# e_Quadratic_3_Level_Boost.net
KiCad netlist of a schematic drawn in EAGLE
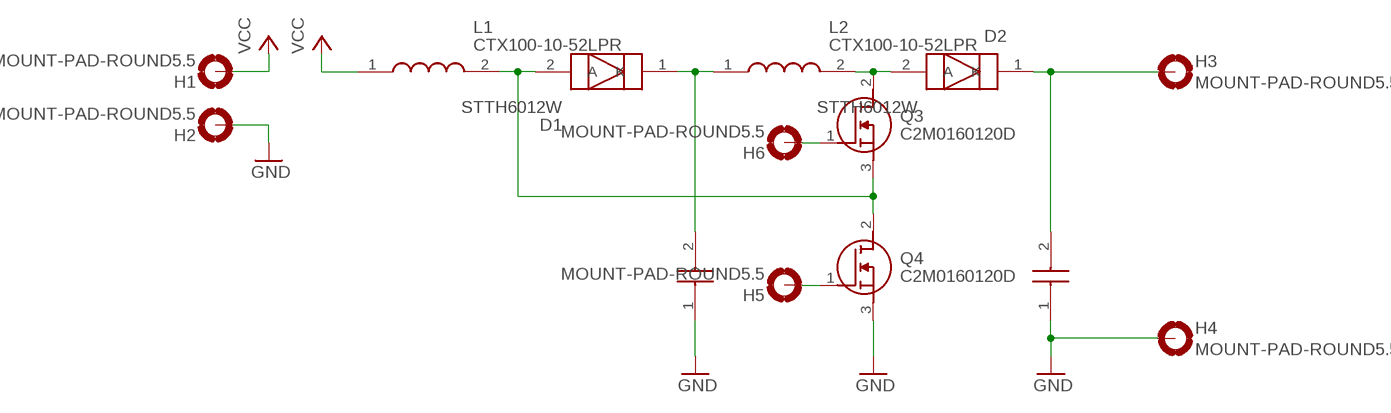
[diagram p0: schematic, sheet 1]

(export (version "E")
  (design (tool "Eeschema 10.0.6"))
  (components
    (comp (ref "D1")
      (value "STTH6012W")
      (footprint "eagle-import:TO1090P515X1560X2445-2P")
      (fields (field (name "RS_PART_NUMBER") "6870818"))
      (libsource (lib "eagle-import") (part "STTH6012W"))
    )
    (comp (ref "D2")
      (value "STTH6012W")
      (footprint "eagle-import:TO1090P515X1560X2445-2P")
      (fields (field (name "RS_PART_NUMBER") "6870818"))
      (libsource (lib "eagle-import") (part "STTH6012W"))
    )
    (comp (ref "H1")
      (value "MOUNT-PAD-ROUND5.5")
      (footprint "eagle-import:5,5-PAD")
      (libsource (lib "eagle-import") (part "MOUNT-PAD-ROUND5.5"))
    )
    (comp (ref "H2")
      (value "MOUNT-PAD-ROUND5.5")
      (footprint "eagle-import:5,5-PAD")
      (libsource (lib "eagle-import") (part "MOUNT-PAD-ROUND5.5"))
    )
    (comp (ref "H3")
      (value "MOUNT-PAD-ROUND5.5")
      (footprint "eagle-import:5,5-PAD")
      (libsource (lib "eagle-import") (part "MOUNT-PAD-ROUND5.5"))
    )
    (comp (ref "H4")
      (value "MOUNT-PAD-ROUND5.5")
      (footprint "eagle-import:5,5-PAD")
      (libsource (lib "eagle-import") (part "MOUNT-PAD-ROUND5.5"))
    )
    (comp (ref "H5")
      (value "MOUNT-PAD-ROUND5.5")
      (footprint "eagle-import:5,5-PAD")
      (libsource (lib "eagle-import") (part "MOUNT-PAD-ROUND5.5"))
    )
    (comp (ref "H6")
      (value "MOUNT-PAD-ROUND5.5")
      (footprint "eagle-import:5,5-PAD")
      (libsource (lib "eagle-import") (part "MOUNT-PAD-ROUND5.5"))
    )
    (comp (ref "L1")
      (value "CTX100-10-52LPR")
      (footprint "eagle-import:CTX1001052LPR")
      (libsource (lib "eagle-import") (part "CTX100-10-52LPR"))
    )
    (comp (ref "L2")
      (value "CTX100-10-52LPR")
      (footprint "eagle-import:CTX1001052LPR")
      (libsource (lib "eagle-import") (part "CTX100-10-52LPR"))
    )
    (comp (ref "Q3")
      (value "C2M0160120D")
      (footprint "eagle-import:TO544P521X1594X2550-3P")
      (fields (field (name "RS_PART_NUMBER") "1629709"))
      (libsource (lib "eagle-import") (part "C2M0160120D"))
    )
    (comp (ref "Q4")
      (value "C2M0160120D")
      (footprint "eagle-import:TO544P521X1594X2550-3P")
      (fields (field (name "RS_PART_NUMBER") "1629709"))
      (libsource (lib "eagle-import") (part "C2M0160120D"))
    )
    (comp (ref "U$1")
      (value "B32774D4505K000")
      (footprint "eagle-import:B32774D4505K000")
      (fields (field (name "RS_PART_NUMBER") "1726009"))
      (libsource (lib "eagle-import") (part "B32774D4505K000"))
    )
    (comp (ref "U$2")
      (value "B32774D4505K000")
      (footprint "eagle-import:B32774D4505K000")
      (fields (field (name "RS_PART_NUMBER") "1726009"))
      (libsource (lib "eagle-import") (part "B32774D4505K000"))
    )
  )
  (nets
    (net (code "1") (name "GND") (class "Default")
      (node (ref "H2") (pin "B5,5") (pinfunction "MOUNT_B5,5") (pintype "passive"))
      (node (ref "H4") (pin "B5,5") (pinfunction "MOUNT_B5,5") (pintype "passive"))
      (node (ref "Q4") (pin "3") (pinfunction "S_3") (pintype "bidirectional"))
      (node (ref "U$1") (pin "1") (pinfunction "1_1") (pintype "bidirectional"))
      (node (ref "U$2") (pin "1") (pinfunction "1_1") (pintype "bidirectional"))
    )
    (net (code "2") (name "Net-(D1-A)") (class "Default")
      (node (ref "D1") (pin "2") (pinfunction "A_2") (pintype "bidirectional"))
      (node (ref "L1") (pin "2") (pinfunction "2_2") (pintype "bidirectional"))
      (node (ref "Q3") (pin "3") (pinfunction "S_3") (pintype "bidirectional"))
      (node (ref "Q4") (pin "2") (pinfunction "D_2") (pintype "bidirectional"))
    )
    (net (code "3") (name "Net-(D1-K)") (class "Default")
      (node (ref "D1") (pin "1") (pinfunction "K_1") (pintype "bidirectional"))
      (node (ref "L2") (pin "1") (pinfunction "1_1") (pintype "bidirectional"))
      (node (ref "U$1") (pin "2") (pinfunction "2_2") (pintype "bidirectional"))
    )
    (net (code "4") (name "Net-(D2-A)") (class "Default")
      (node (ref "D2") (pin "2") (pinfunction "A_2") (pintype "bidirectional"))
      (node (ref "L2") (pin "2") (pinfunction "2_2") (pintype "bidirectional"))
      (node (ref "Q3") (pin "2") (pinfunction "D_2") (pintype "bidirectional"))
    )
    (net (code "5") (name "Net-(D2-K)") (class "Default")
      (node (ref "D2") (pin "1") (pinfunction "K_1") (pintype "bidirectional"))
      (node (ref "H3") (pin "B5,5") (pinfunction "MOUNT_B5,5") (pintype "passive"))
      (node (ref "U$2") (pin "2") (pinfunction "2_2") (pintype "bidirectional"))
    )
    (net (code "6") (name "Net-(H5-MOUNT)") (class "Default")
      (node (ref "H5") (pin "B5,5") (pinfunction "MOUNT_B5,5") (pintype "passive"))
      (node (ref "Q4") (pin "1") (pinfunction "G_1") (pintype "bidirectional"))
    )
    (net (code "7") (name "Net-(H6-MOUNT)") (class "Default")
      (node (ref "H6") (pin "B5,5") (pinfunction "MOUNT_B5,5") (pintype "passive"))
      (node (ref "Q3") (pin "1") (pinfunction "G_1") (pintype "bidirectional"))
    )
    (net (code "8") (name "VCC") (class "Default")
      (node (ref "H1") (pin "B5,5") (pinfunction "MOUNT_B5,5") (pintype "passive"))
      (node (ref "L1") (pin "1") (pinfunction "1_1") (pintype "bidirectional"))
    )
  )
)
